# Side_Long.net
KiCad netlist of a schematic drawn in EAGLE
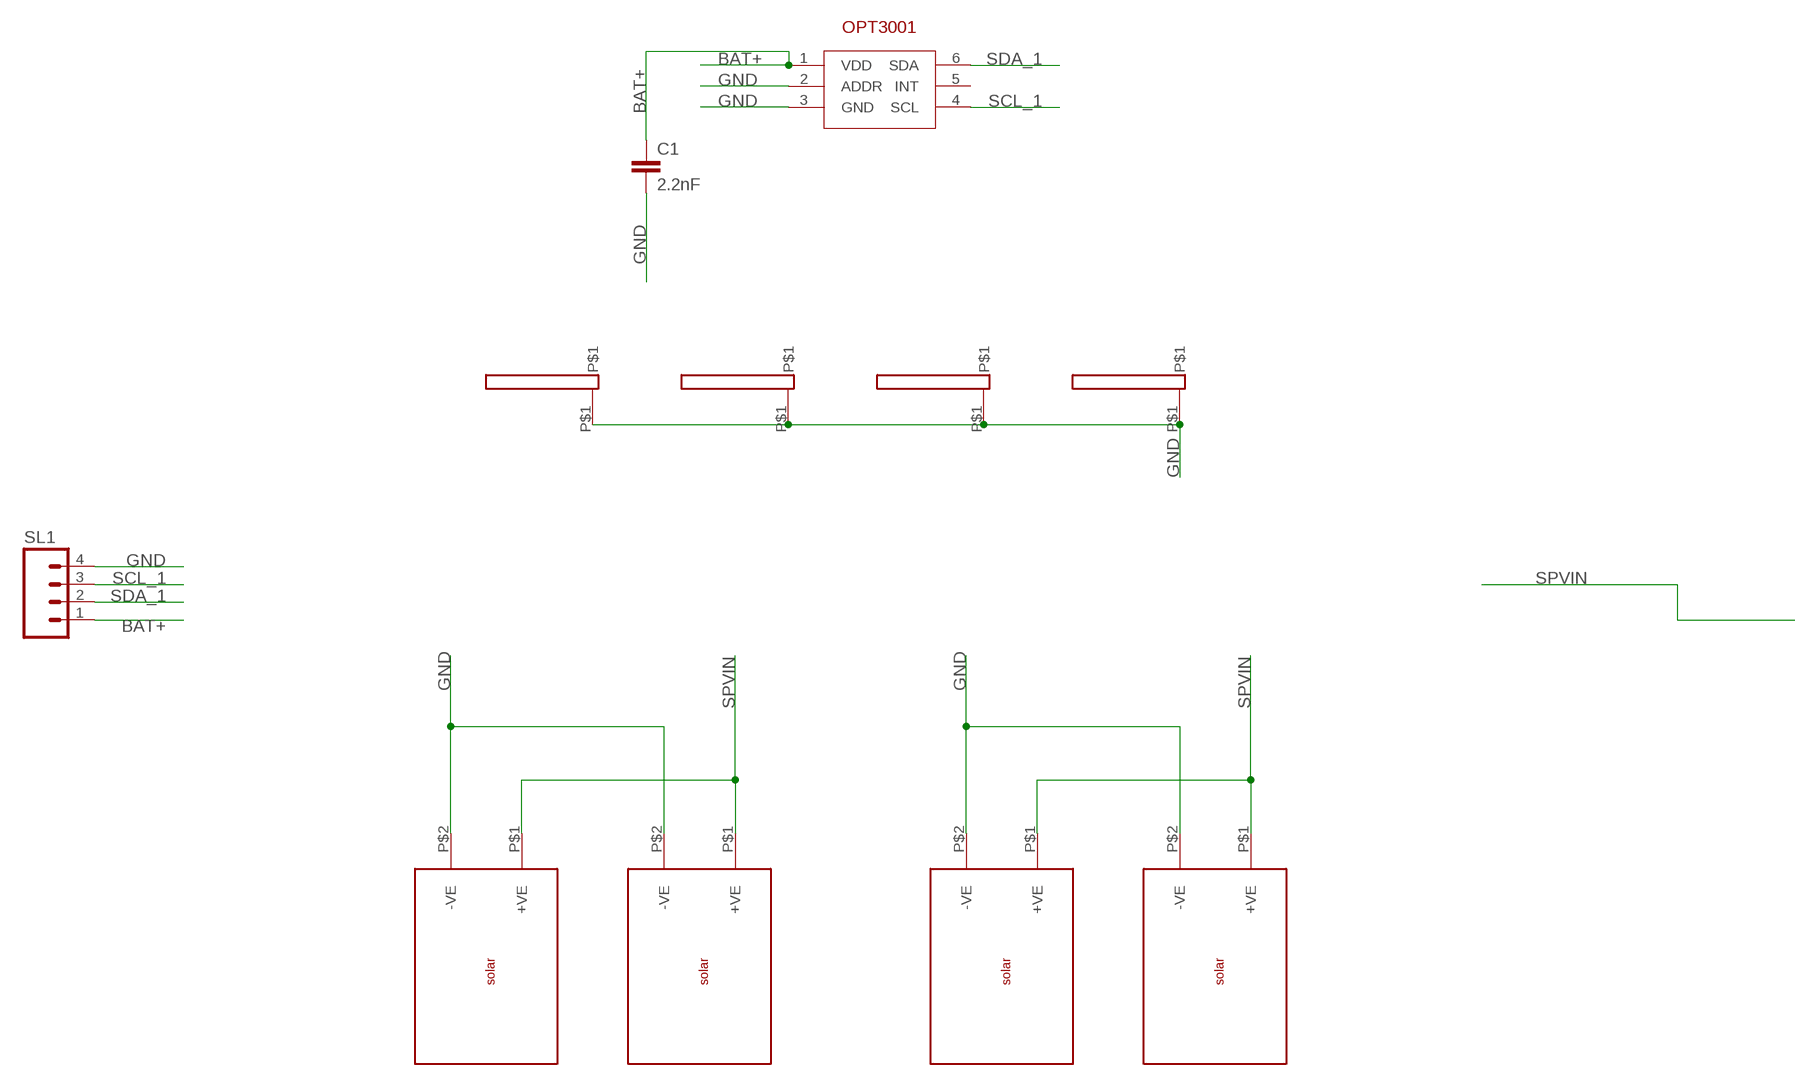
[diagram p0: schematic, sheet 1, part 1 of 2]
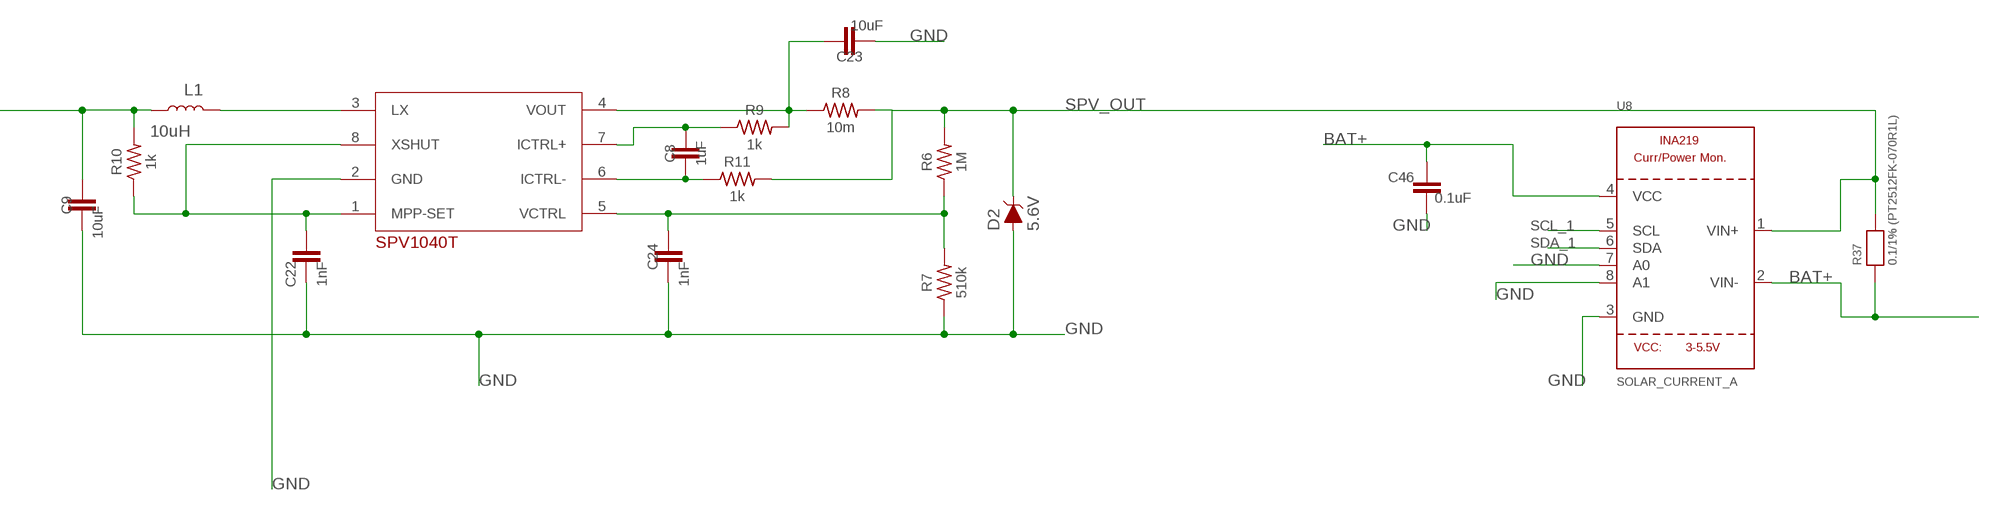
[diagram p1: schematic, sheet 1, part 2 of 2]

(export (version "E")
  (design (tool "Eeschema 10.0.6"))
  (components
    (comp (ref "C1")
      (value "2.2nF")
      (footprint "eagle-import:0603")
      (libsource (lib "eagle-import") (part "2.2NF/2200PF-0603-50V-10%"))
    )
    (comp (ref "C8")
      (value "1uF")
      (footprint "eagle-import:0603")
      (libsource (lib "eagle-import") (part "10UF-0603-6.3V-20%"))
    )
    (comp (ref "C9")
      (value "10uF")
      (footprint "eagle-import:0603")
      (libsource (lib "eagle-import") (part "10UF-0603-6.3V-20%"))
    )
    (comp (ref "C22")
      (value "1nF")
      (footprint "eagle-import:0603")
      (libsource (lib "eagle-import") (part "10UF-0603-6.3V-20%"))
    )
    (comp (ref "C23")
      (value "10uF")
      (footprint "eagle-import:0603")
      (libsource (lib "eagle-import") (part "10UF-0603-6.3V-20%"))
    )
    (comp (ref "C24")
      (value "1nF")
      (footprint "eagle-import:0603")
      (libsource (lib "eagle-import") (part "10UF-0603-6.3V-20%"))
    )
    (comp (ref "C46")
      (value "0.1uF")
      (footprint "eagle-import:0603")
      (libsource (lib "eagle-import") (part "10UF-0603-6.3V-20%"))
    )
    (comp (ref "D2")
      (value "5.6V")
      (footprint "eagle-import:SOD-323")
      (libsource (lib "eagle-import") (part "DIODE-ZENER-MMSZ5232BS"))
    )
    (comp (ref "L1")
      (value "10uH")
      (footprint "eagle-import:0603")
      (libsource (lib "eagle-import") (part "INDUCTOR-0603-33NH"))
    )
    (comp (ref "R6")
      (value "1M")
      (footprint "eagle-import:RES_0603")
      (fields
        (field (name "DIGIKEY_PART_NUMBER") "311-0.0GRTR-ND")
        (field (name "MANUFACTURER") "Yageo")
        (field (name "MPN") "RC0603JR-070RL")
        (field (name "CREATED_BY") "PCBLayout.com")
      )
      (libsource (lib "eagle-import") (part "RC0603JR-070RL"))
    )
    (comp (ref "R7")
      (value "510k")
      (footprint "eagle-import:RES_0603")
      (fields
        (field (name "DIGIKEY_PART_NUMBER") "311-0.0GRTR-ND")
        (field (name "MANUFACTURER") "Yageo")
        (field (name "MPN") "RC0603JR-070RL")
        (field (name "CREATED_BY") "PCBLayout.com")
      )
      (libsource (lib "eagle-import") (part "RC0603JR-070RL"))
    )
    (comp (ref "R8")
      (value "10m")
      (footprint "eagle-import:RES_0603")
      (fields
        (field (name "DIGIKEY_PART_NUMBER") "311-0.0GRTR-ND")
        (field (name "MANUFACTURER") "Yageo")
        (field (name "MPN") "RC0603JR-070RL")
        (field (name "CREATED_BY") "PCBLayout.com")
      )
      (libsource (lib "eagle-import") (part "RC0603JR-070RL"))
    )
    (comp (ref "R9")
      (value "1k")
      (footprint "eagle-import:RES_0603")
      (fields
        (field (name "DIGIKEY_PART_NUMBER") "311-0.0GRTR-ND")
        (field (name "MANUFACTURER") "Yageo")
        (field (name "MPN") "RC0603JR-070RL")
        (field (name "CREATED_BY") "PCBLayout.com")
      )
      (libsource (lib "eagle-import") (part "RC0603JR-070RL"))
    )
    (comp (ref "R10")
      (value "1k")
      (footprint "eagle-import:RES_0603")
      (fields
        (field (name "DIGIKEY_PART_NUMBER") "311-0.0GRTR-ND")
        (field (name "MANUFACTURER") "Yageo")
        (field (name "MPN") "RC0603JR-070RL")
        (field (name "CREATED_BY") "PCBLayout.com")
      )
      (libsource (lib "eagle-import") (part "RC0603JR-070RL"))
    )
    (comp (ref "R11")
      (value "1k")
      (footprint "eagle-import:RES_0603")
      (fields
        (field (name "DIGIKEY_PART_NUMBER") "311-0.0GRTR-ND")
        (field (name "MANUFACTURER") "Yageo")
        (field (name "MPN") "RC0603JR-070RL")
        (field (name "CREATED_BY") "PCBLayout.com")
      )
      (libsource (lib "eagle-import") (part "RC0603JR-070RL"))
    )
    (comp (ref "R37")
      (value "0.1/1% (PT2512FK-070R1L)")
      (footprint "eagle-import:2512")
      (libsource (lib "eagle-import") (part "RESISTOR2512"))
    )
    (comp (ref "SL1")
      (value "M04")
      (footprint "eagle-import:04P")
      (libsource (lib "eagle-import") (part "M04"))
    )
    (comp (ref "SPV_A")
      (value "SPV1040T_")
      (footprint "eagle-import:SOP65P640X120-8N")
      (libsource (lib "eagle-import") (part "SPV1040T_"))
    )
    (comp (ref "U$1")
      (value "SOLAR_50_5_2")
      (footprint "eagle-import:FOOT")
      (libsource (lib "eagle-import") (part "SOLAR_50_5_2"))
    )
    (comp (ref "U$2")
      (value "SOLAR_50_5_2")
      (footprint "eagle-import:FOOT")
      (libsource (lib "eagle-import") (part "SOLAR_50_5_2"))
    )
    (comp (ref "U$3")
      (value "16X2")
      (footprint "eagle-import:16X2")
      (libsource (lib "eagle-import") (part "16X2"))
    )
    (comp (ref "U$4")
      (value "16X2")
      (footprint "eagle-import:16X2")
      (libsource (lib "eagle-import") (part "16X2"))
    )
    (comp (ref "U$5")
      (value "16X2")
      (footprint "eagle-import:16X2")
      (libsource (lib "eagle-import") (part "16X2"))
    )
    (comp (ref "U$6")
      (value "16X2")
      (footprint "eagle-import:16X2")
      (libsource (lib "eagle-import") (part "16X2"))
    )
    (comp (ref "U$7")
      (value "SOLAR_50_5_2")
      (footprint "eagle-import:FOOT")
      (libsource (lib "eagle-import") (part "SOLAR_50_5_2"))
    )
    (comp (ref "U$8")
      (value "SOLAR_50_5_2")
      (footprint "eagle-import:FOOT")
      (libsource (lib "eagle-import") (part "SOLAR_50_5_2"))
    )
    (comp (ref "U1")
      (value "SON65P200X200X65-7N")
      (footprint "eagle-import:SON65P200X200X65-7N")
      (fields (field (name "MANUFACTURER") "Maxim Integrated"))
      (libsource (lib "eagle-import") (part "SON65P200X200X65-7N"))
    )
    (comp (ref "U8")
      (value "SOLAR_CURRENT_A")
      (footprint "eagle-import:SOT23-8")
      (libsource (lib "eagle-import") (part "INA219"))
    )
  )
  (nets
    (net (code "1") (name "/BAT+") (class "Default")
      (node (ref "C1") (pin "1") (pinfunction "1_1") (pintype "passive"))
      (node (ref "C46") (pin "1") (pinfunction "1_1") (pintype "passive"))
      (node (ref "R37") (pin "1") (pinfunction "1_1") (pintype "passive"))
      (node (ref "SL1") (pin "1") (pinfunction "1_1") (pintype "passive"))
      (node (ref "U1") (pin "1") (pinfunction "VDD_1") (pintype "bidirectional"))
      (node (ref "U8") (pin "2") (pinfunction "VIN-_2") (pintype "bidirectional"))
      (node (ref "U8") (pin "4") (pinfunction "VCC_4") (pintype "bidirectional"))
    )
    (net (code "2") (name "/GND") (class "Default")
      (node (ref "C1") (pin "2") (pinfunction "2_2") (pintype "passive"))
      (node (ref "C22") (pin "2") (pinfunction "2_2") (pintype "passive"))
      (node (ref "C23") (pin "2") (pinfunction "2_2") (pintype "passive"))
      (node (ref "C24") (pin "2") (pinfunction "2_2") (pintype "passive"))
      (node (ref "C46") (pin "2") (pinfunction "2_2") (pintype "passive"))
      (node (ref "C9") (pin "2") (pinfunction "2_2") (pintype "passive"))
      (node (ref "D2") (pin "A") (pinfunction "A_A") (pintype "passive"))
      (node (ref "R7") (pin "1") (pinfunction "1_1") (pintype "passive"))
      (node (ref "SL1") (pin "4") (pinfunction "4_4") (pintype "passive"))
      (node (ref "SPV_A") (pin "2") (pinfunction "GND_2") (pintype "bidirectional"))
      (node (ref "U$1") (pin "P$2") (pinfunction "-VE_P$2") (pintype "bidirectional"))
      (node (ref "U$2") (pin "P$2") (pinfunction "-VE_P$2") (pintype "bidirectional"))
      (node (ref "U$3") (pin "P$1") (pinfunction "P$1_P$1") (pintype "bidirectional"))
      (node (ref "U$4") (pin "P$1") (pinfunction "P$1_P$1") (pintype "bidirectional"))
      (node (ref "U$5") (pin "P$1") (pinfunction "P$1_P$1") (pintype "bidirectional"))
      (node (ref "U$6") (pin "P$1") (pinfunction "P$1_P$1") (pintype "bidirectional"))
      (node (ref "U$7") (pin "P$2") (pinfunction "-VE_P$2") (pintype "bidirectional"))
      (node (ref "U$8") (pin "P$2") (pinfunction "-VE_P$2") (pintype "bidirectional"))
      (node (ref "U1") (pin "2") (pinfunction "ADDR_2") (pintype "bidirectional"))
      (node (ref "U1") (pin "3") (pinfunction "GND_3") (pintype "bidirectional"))
      (node (ref "U8") (pin "3") (pinfunction "GND_3") (pintype "bidirectional"))
      (node (ref "U8") (pin "7") (pinfunction "A0_7") (pintype "bidirectional"))
      (node (ref "U8") (pin "8") (pinfunction "A1_8") (pintype "bidirectional"))
    )
    (net (code "3") (name "/SCL_1") (class "Default")
      (node (ref "SL1") (pin "3") (pinfunction "3_3") (pintype "passive"))
      (node (ref "U1") (pin "4") (pinfunction "SCL_4") (pintype "bidirectional"))
      (node (ref "U8") (pin "5") (pinfunction "SCL_5") (pintype "bidirectional"))
    )
    (net (code "4") (name "/SDA_1") (class "Default")
      (node (ref "SL1") (pin "2") (pinfunction "2_2") (pintype "passive"))
      (node (ref "U1") (pin "6") (pinfunction "SDA_6") (pintype "bidirectional"))
      (node (ref "U8") (pin "6") (pinfunction "SDA_6") (pintype "bidirectional"))
    )
    (net (code "5") (name "/SPVIN") (class "Default")
      (node (ref "C9") (pin "1") (pinfunction "1_1") (pintype "passive"))
      (node (ref "L1") (pin "1") (pinfunction "1_1") (pintype "passive"))
      (node (ref "R10") (pin "2") (pinfunction "2_2") (pintype "passive"))
      (node (ref "U$1") (pin "P$1") (pinfunction "+VE_P$1") (pintype "bidirectional"))
      (node (ref "U$2") (pin "P$1") (pinfunction "+VE_P$1") (pintype "bidirectional"))
      (node (ref "U$7") (pin "P$1") (pinfunction "+VE_P$1") (pintype "bidirectional"))
      (node (ref "U$8") (pin "P$1") (pinfunction "+VE_P$1") (pintype "bidirectional"))
    )
    (net (code "6") (name "/SPV_OUT") (class "Default")
      (node (ref "D2") (pin "C") (pinfunction "C_C") (pintype "passive"))
      (node (ref "R11") (pin "2") (pinfunction "2_2") (pintype "passive"))
      (node (ref "R37") (pin "2") (pinfunction "2_2") (pintype "passive"))
      (node (ref "R6") (pin "2") (pinfunction "2_2") (pintype "passive"))
      (node (ref "R8") (pin "2") (pinfunction "2_2") (pintype "passive"))
      (node (ref "U8") (pin "1") (pinfunction "VIN+_1") (pintype "bidirectional"))
    )
    (net (code "7") (name "Net-(SPV_A-ICTRL+)") (class "Default")
      (node (ref "C8") (pin "1") (pinfunction "1_1") (pintype "passive"))
      (node (ref "R9") (pin "1") (pinfunction "1_1") (pintype "passive"))
      (node (ref "SPV_A") (pin "7") (pinfunction "ICTRL+_7") (pintype "bidirectional"))
    )
    (net (code "8") (name "Net-(SPV_A-ICTRL-)") (class "Default")
      (node (ref "C8") (pin "2") (pinfunction "2_2") (pintype "passive"))
      (node (ref "R11") (pin "1") (pinfunction "1_1") (pintype "passive"))
      (node (ref "SPV_A") (pin "6") (pinfunction "ICTRL-_6") (pintype "bidirectional"))
    )
    (net (code "9") (name "Net-(SPV_A-LX)") (class "Default")
      (node (ref "L1") (pin "2") (pinfunction "2_2") (pintype "passive"))
      (node (ref "SPV_A") (pin "3") (pinfunction "LX_3") (pintype "bidirectional"))
    )
    (net (code "10") (name "Net-(SPV_A-MPP-SET)") (class "Default")
      (node (ref "C22") (pin "1") (pinfunction "1_1") (pintype "passive"))
      (node (ref "R10") (pin "1") (pinfunction "1_1") (pintype "passive"))
      (node (ref "SPV_A") (pin "1") (pinfunction "MPP-SET_1") (pintype "bidirectional"))
      (node (ref "SPV_A") (pin "8") (pinfunction "XSHUT_8") (pintype "bidirectional"))
    )
    (net (code "11") (name "Net-(SPV_A-VCTRL)") (class "Default")
      (node (ref "C24") (pin "1") (pinfunction "1_1") (pintype "passive"))
      (node (ref "R6") (pin "1") (pinfunction "1_1") (pintype "passive"))
      (node (ref "R7") (pin "2") (pinfunction "2_2") (pintype "passive"))
      (node (ref "SPV_A") (pin "5") (pinfunction "VCTRL_5") (pintype "bidirectional"))
    )
    (net (code "12") (name "Net-(SPV_A-VOUT)") (class "Default")
      (node (ref "C23") (pin "1") (pinfunction "1_1") (pintype "passive"))
      (node (ref "R8") (pin "1") (pinfunction "1_1") (pintype "passive"))
      (node (ref "R9") (pin "2") (pinfunction "2_2") (pintype "passive"))
      (node (ref "SPV_A") (pin "4") (pinfunction "VOUT_4") (pintype "bidirectional"))
    )
    (net (code "13") (name "unconnected-(U1-INT-Pad5)") (class "Default")
      (node (ref "U1") (pin "5") (pinfunction "INT_5") (pintype "bidirectional"))
    )
  )
)
